# Power_And_Driver.net
KiCad netlist of a schematic drawn in Altium Designer
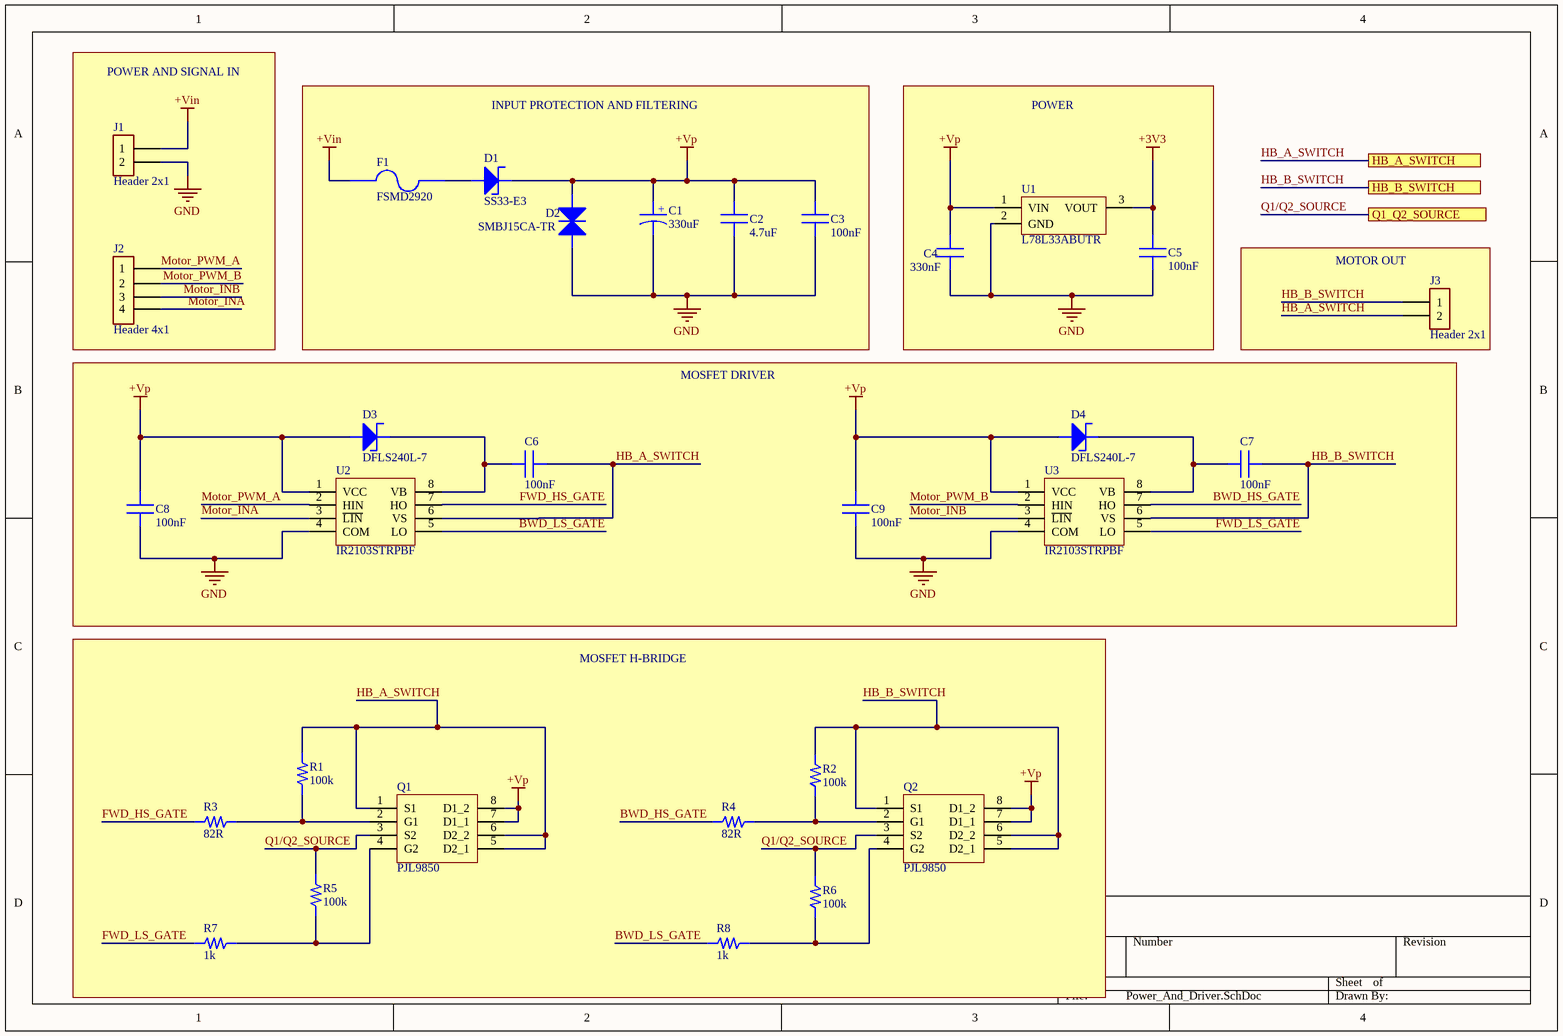
[diagram p0: Power_And_Driver.SchDoc]

(export (version "E")
  (design (tool "Eeschema 10.0.6"))
  (components
    (comp (ref "C1")
      (value "330uF")
      (footprint "CAP_EEEFK1V331P")
      (description "330 µF 35 V Aluminum Electrolytic Capacitors Radial, Can - SMD 2000 Hrs @ 105°C")
      (fields (field (name "TOLERANCE") "±20%") (field (name "MANUFACTURER") "Panasonic Industry"))
      (libsource (lib "Chicken_Coop_Door_Main_Board_V3") (part "CAP Electrolytic EEE-FK1V331P"))
    )
    (comp (ref "C2")
      (value "4.7uF")
      (footprint "CAPC2012X145N 0805")
      (description "MLCC (2012) 0805 4.7uF 16VDC ±10% X7R AUTOMOTIVE")
      (fields (field (name "TOLERANCE") "±10 %") (field (name "MANUFACTURER") "SAMSUNG"))
      (libsource (lib "Chicken_Coop_Door_Main_Board_V3") (part "CAP 0805 4.7uF CL21B475KOQVPNE"))
    )
    (comp (ref "C3")
      (value "100nF")
      (footprint "CAPC2012X145N 0805")
      (description "MLCC 0805 100nF 50VDC ±10% X7R")
      (fields (field (name "TOLERANCE") "±5 %") (field (name "MANUFACTURER") "YAGEO"))
      (libsource (lib "Chicken_Coop_Door_Main_Board_V3") (part "CAP 0805 100nF CC0805JRX7R9BB104"))
    )
    (comp (ref "C4")
      (value "330nF")
      (footprint "CAPC2012X145N 0805")
      (description "MLCC (2012) 0805 330nF 50VDC ±10% X7R")
      (fields (field (name "TOLERANCE") "±10 %") (field (name "MANUFACTURER") "SAMSUNG"))
      (libsource (lib "Chicken_Coop_Door_Main_Board_V3") (part "CAP 0805 330nF CL21B334KBFNNNE"))
    )
    (comp (ref "C5")
      (value "100nF")
      (footprint "CAPC2012X145N 0805")
      (description "MLCC 0805 100nF 50VDC ±10% X7R")
      (fields (field (name "TOLERANCE") "±5 %") (field (name "MANUFACTURER") "YAGEO"))
      (libsource (lib "Chicken_Coop_Door_Main_Board_V3") (part "CAP 0805 100nF CC0805JRX7R9BB104"))
    )
    (comp (ref "C6")
      (value "100nF")
      (footprint "CAPC2012X145N 0805")
      (description "MLCC 0805 100nF 50VDC ±10% X7R")
      (fields (field (name "TOLERANCE") "±5 %") (field (name "MANUFACTURER") "YAGEO"))
      (libsource (lib "Chicken_Coop_Door_Main_Board_V3") (part "CAP 0805 100nF CC0805JRX7R9BB104"))
    )
    (comp (ref "C7")
      (value "100nF")
      (footprint "CAPC2012X145N 0805")
      (description "MLCC 0805 100nF 50VDC ±10% X7R")
      (fields (field (name "TOLERANCE") "±5 %") (field (name "MANUFACTURER") "YAGEO"))
      (libsource (lib "Chicken_Coop_Door_Main_Board_V3") (part "CAP 0805 100nF CC0805JRX7R9BB104"))
    )
    (comp (ref "C8")
      (value "100nF")
      (footprint "CAPC2012X145N 0805")
      (description "MLCC 0805 100nF 50VDC ±10% X7R")
      (fields (field (name "TOLERANCE") "±5 %") (field (name "MANUFACTURER") "YAGEO"))
      (libsource (lib "Chicken_Coop_Door_Main_Board_V3") (part "CAP 0805 100nF CC0805JRX7R9BB104"))
    )
    (comp (ref "C9")
      (value "100nF")
      (footprint "CAPC2012X145N 0805")
      (description "MLCC 0805 100nF 50VDC ±10% X7R")
      (fields (field (name "TOLERANCE") "±5 %") (field (name "MANUFACTURER") "YAGEO"))
      (libsource (lib "Chicken_Coop_Door_Main_Board_V3") (part "CAP 0805 100nF CC0805JRX7R9BB104"))
    )
    (comp (ref "D1")
      (value "SS33-E3")
      (footprint "SS33-E3/57T Schottky Diode")
      (description "DIODE SCHOTTKY 30V 3A DO214AB")
      (fields (field (name "MANUFACTURER") "Vishay General Semiconductor - Diodes Division"))
      (libsource (lib "Chicken_Coop_Door_Main_Board_V3") (part "DIODE SCHOTTKY SS33-E3/57T"))
    )
    (comp (ref "D2")
      (value "SMBJ15CA-TR")
      (footprint "TVS DIODE SMBJ15CA-TR")
      (description "24.4V Clamp 25.1A Ipp Tvs Diode Surface Mount SMB")
      (fields (field (name "MANUFACTURER") "STMicroelectronics"))
      (libsource (lib "Chicken_Coop_Door_Main_Board_V3") (part "TVS DIODE SMBJ15CA-TR"))
    )
    (comp (ref "D3")
      (value "DFLS240L-7")
      (footprint "DIODE DFLS240L-7  POWERDI 123")
      (description "DIODE SCHOTTK 40V 2A POWERDI 123")
      (fields (field (name "MANUFACTURER") "Diodes Incorporated"))
      (libsource (lib "Chicken_Coop_Door_Main_Board_V3") (part "DIODE SCHOTTKY DFLS240L-7"))
    )
    (comp (ref "D4")
      (value "DFLS240L-7")
      (footprint "DIODE DFLS240L-7  POWERDI 123")
      (description "DIODE SCHOTTK 40V 2A POWERDI 123")
      (fields (field (name "MANUFACTURER") "Diodes Incorporated"))
      (libsource (lib "Chicken_Coop_Door_Main_Board_V3") (part "DIODE SCHOTTKY DFLS240L-7"))
    )
    (comp (ref "F1")
      (value "FSMD2920")
      (footprint "FUSE FSMD200-24-2920-R")
      (description "PTC Resettable Fuse 24V 2 A Ih Surface Mount 2920 (7351 Metric), Concave")
      (fields (field (name "MANUFACTURER") "RFE/Fuzetec"))
      (libsource (lib "Chicken_Coop_Door_Main_Board_V3") (part "FUSE FSMD200-24-2920-R"))
    )
    (comp (ref "J1")
      (value "Header 2x1")
      (footprint "2x1 Terminal Block")
      (description "TERM.BLK.5.00MM 2P PCB TYPE GREEN")
      (fields (field (name "MANUFACTURER") "DEGSON") (field (name "VOLTAGE") "300V"))
      (libsource (lib "Chicken_Coop_Door_Main_Board_V3") (part "Terminal Block 2x1"))
    )
    (comp (ref "J2")
      (value "Header 4x1")
      (footprint "JST_B4B-PH-K-S 1x4 Header")
      (description "CON.T.B.2MM 4P 180C MALE WHITE CONNFLY")
      (fields (field (name "MANUFACTURER") "CONNFLY"))
      (libsource (lib "Chicken_Coop_Door_Main_Board_V3") (part "Header 4x1 DS1066-4MVW6X"))
    )
    (comp (ref "J3")
      (value "Header 2x1")
      (footprint "2x1 Terminal Block")
      (description "TERM.BLK.5.00MM 2P PCB TYPE GREEN")
      (fields (field (name "MANUFACTURER") "DEGSON") (field (name "VOLTAGE") "300V"))
      (libsource (lib "") (part "Terminal Block 2x1_1"))
    )
    (comp (ref "Q1")
      (value "PJL9850")
      (footprint "PJL850 N-CH MOSFET")
      (description "Low Voltage MOSFET (20-40V,Rds(on)<1) - PJL9850 , N/N Channel, Dual, 5.4A, 40V, SOP-8")
      (fields (field (name "MANUFACTURER") "PANJIT"))
      (libsource (lib "Chicken_Coop_Door_Main_Board_V3") (part "PJL9850 N-Ch MOSFET"))
    )
    (comp (ref "Q2")
      (value "PJL9850")
      (footprint "PJL850 N-CH MOSFET")
      (description "Low Voltage MOSFET (20-40V,Rds(on)<1) - PJL9850 , N/N Channel, Dual, 5.4A, 40V, SOP-8")
      (fields (field (name "MANUFACTURER") "PANJIT"))
      (libsource (lib "Chicken_Coop_Door_Main_Board_V3") (part "PJL9850 N-Ch MOSFET"))
    )
    (comp (ref "R1")
      (value "100k")
      (footprint "RES 0603 ROYALOHM")
      (description "RES.(1608) 0603 100K Ohms 1% 1/10W-S 100PPM")
      (fields (field (name "TOLERANCE") "±5 %") (field (name "MANUFACTURER") "ROYALOHM"))
      (libsource (lib "Chicken_Coop_Door_Main_Board_V3") (part "RES 0603 100k 0603SAF1003T5E"))
    )
    (comp (ref "R2")
      (value "100k")
      (footprint "RES 0603 ROYALOHM")
      (description "RES.(1608) 0603 100K Ohms 1% 1/10W-S 100PPM")
      (fields (field (name "TOLERANCE") "±5 %") (field (name "MANUFACTURER") "ROYALOHM"))
      (libsource (lib "Chicken_Coop_Door_Main_Board_V3") (part "RES 0603 100k 0603SAF1003T5E"))
    )
    (comp (ref "R3")
      (value "82R")
      (footprint "RES 0805 YAGEO C2012X60N")
      (description "RES.(2012) 0805 82 Ohms 5% 1/8W-S 200PPM")
      (fields (field (name "POWER") "1/8W") (field (name "TOLERANCE") "±1 %"))
      (libsource (lib "Chicken_Coop_Door_Main_Board_V3") (part "RES 0805 82 Ohms 0805S8J0820T5E"))
    )
    (comp (ref "R4")
      (value "82R")
      (footprint "RES 0805 YAGEO C2012X60N")
      (description "RES.(2012) 0805 82 Ohms 5% 1/8W-S 200PPM")
      (fields (field (name "POWER") "1/8W") (field (name "TOLERANCE") "±1 %"))
      (libsource (lib "Chicken_Coop_Door_Main_Board_V3") (part "RES 0805 82 Ohms 0805S8J0820T5E"))
    )
    (comp (ref "R5")
      (value "100k")
      (footprint "RES 0603 ROYALOHM")
      (description "RES.(1608) 0603 100K Ohms 1% 1/10W-S 100PPM")
      (fields (field (name "TOLERANCE") "±5 %") (field (name "MANUFACTURER") "ROYALOHM"))
      (libsource (lib "Chicken_Coop_Door_Main_Board_V3") (part "RES 0603 100k 0603SAF1003T5E"))
    )
    (comp (ref "R6")
      (value "100k")
      (footprint "RES 0603 ROYALOHM")
      (description "RES.(1608) 0603 100K Ohms 1% 1/10W-S 100PPM")
      (fields (field (name "TOLERANCE") "±5 %") (field (name "MANUFACTURER") "ROYALOHM"))
      (libsource (lib "Chicken_Coop_Door_Main_Board_V3") (part "RES 0603 100k 0603SAF1003T5E"))
    )
    (comp (ref "R7")
      (value "1k")
      (footprint "RES 0805 YAGEO C2012X60N")
      (description "RES.(2012) 0805 1K Ohms 1% 1/8W-S 100PPM")
      (fields (field (name "POWER") "1/8W") (field (name "TOLERANCE") "±1 %"))
      (libsource (lib "Chicken_Coop_Door_Main_Board_V3") (part "RES 0805 1k Ohms 0805S8F1001TDE"))
    )
    (comp (ref "R8")
      (value "1k")
      (footprint "RES 0805 YAGEO C2012X60N")
      (description "RES.(2012) 0805 1K Ohms 1% 1/8W-S 100PPM")
      (fields (field (name "POWER") "1/8W") (field (name "TOLERANCE") "±1 %"))
      (libsource (lib "Chicken_Coop_Door_Main_Board_V3") (part "RES 0805 1k Ohms 0805S8F1001TDE"))
    )
    (comp (ref "U1")
      (value "L78L33ABUTR")
      (footprint "LDO L78L33ABUTR SOT89")
      (description "Linear Voltage Regulator IC Positive Fixed 1 Output 100mA SOT-89-3")
      (fields (field (name "MANUFACTURER") "STMicroelectronics"))
      (libsource (lib "Chicken_Coop_Door_Main_Board_V3") (part "LDO L78L33ABUTR"))
    )
    (comp (ref "U2")
      (value "IR2103STRPBF")
      (footprint "IR2103STRPBF Half Bridge Mosfet Driver")
      (description "Half-Bridge Gate Driver IC Inverting, Non-Inverting 8-SOIC")
      (fields (field (name "MANUFACTURER") "Infineon Technologies"))
      (libsource (lib "Chicken_Coop_Door_Main_Board_V3") (part "IR2103STRPBF Half Bridge MOSFET Driver"))
    )
    (comp (ref "U3")
      (value "IR2103STRPBF")
      (footprint "IR2103STRPBF Half Bridge Mosfet Driver")
      (description "Half-Bridge Gate Driver IC Inverting, Non-Inverting 8-SOIC")
      (fields (field (name "MANUFACTURER") "Infineon Technologies"))
      (libsource (lib "Chicken_Coop_Door_Main_Board_V3") (part "IR2103STRPBF Half Bridge MOSFET Driver"))
    )
  )
  (nets
    (net (code "1") (name "+3V3") (class "Default")
      (node (ref "C5") (pin "2") (pinfunction "2_2") (pintype "passive"))
      (node (ref "U1") (pin "3") (pinfunction "VOUT_3") (pintype "passive"))
    )
    (net (code "2") (name "+Vin") (class "Default")
      (node (ref "F1") (pin "1") (pinfunction "1_1") (pintype "passive"))
      (node (ref "J1") (pin "1") (pinfunction "1_1") (pintype "passive"))
    )
    (net (code "3") (name "+Vp") (class "Default")
      (node (ref "C1") (pin "1") (pinfunction "1_1") (pintype "passive"))
      (node (ref "C2") (pin "2") (pinfunction "2_2") (pintype "passive"))
      (node (ref "C3") (pin "2") (pinfunction "2_2") (pintype "passive"))
      (node (ref "C4") (pin "2") (pinfunction "2_2") (pintype "passive"))
      (node (ref "C8") (pin "2") (pinfunction "2_2") (pintype "passive"))
      (node (ref "C9") (pin "2") (pinfunction "2_2") (pintype "passive"))
      (node (ref "D1") (pin "K") (pinfunction "Cathode_K") (pintype "passive"))
      (node (ref "D2") (pin "2") (pinfunction "C_2") (pintype "passive"))
      (node (ref "D3") (pin "1") (pinfunction "Anode_1") (pintype "passive"))
      (node (ref "D4") (pin "1") (pinfunction "Anode_1") (pintype "passive"))
      (node (ref "Q1") (pin "7") (pinfunction "D1_1_7") (pintype "passive"))
      (node (ref "Q1") (pin "8") (pinfunction "D1_2_8") (pintype "passive"))
      (node (ref "Q2") (pin "7") (pinfunction "D1_1_7") (pintype "passive"))
      (node (ref "Q2") (pin "8") (pinfunction "D1_2_8") (pintype "passive"))
      (node (ref "U1") (pin "1") (pinfunction "VIN_1") (pintype "passive"))
      (node (ref "U2") (pin "1") (pinfunction "VCC_1") (pintype "passive"))
      (node (ref "U3") (pin "1") (pinfunction "VCC_1") (pintype "passive"))
    )
    (net (code "4") (name "/BWD_HS_GATE") (class "Default")
      (node (ref "R4") (pin "1") (pinfunction "1_1") (pintype "passive"))
      (node (ref "U3") (pin "7") (pinfunction "HO_7") (pintype "passive"))
    )
    (net (code "5") (name "/BWD_LS_GATE") (class "Default")
      (node (ref "R8") (pin "1") (pinfunction "1_1") (pintype "passive"))
      (node (ref "U2") (pin "5") (pinfunction "LO_5") (pintype "passive"))
    )
    (net (code "6") (name "/FWD_HS_GATE") (class "Default")
      (node (ref "R3") (pin "1") (pinfunction "1_1") (pintype "passive"))
      (node (ref "U2") (pin "7") (pinfunction "HO_7") (pintype "passive"))
    )
    (net (code "7") (name "/FWD_LS_GATE") (class "Default")
      (node (ref "R7") (pin "1") (pinfunction "1_1") (pintype "passive"))
      (node (ref "U3") (pin "5") (pinfunction "LO_5") (pintype "passive"))
    )
    (net (code "8") (name "/HB_A_SWITCH") (class "Default")
      (node (ref "C6") (pin "1") (pinfunction "1_1") (pintype "passive"))
      (node (ref "J3") (pin "2") (pinfunction "2_2") (pintype "passive"))
      (node (ref "Q1") (pin "1") (pinfunction "S1_1") (pintype "passive"))
      (node (ref "Q1") (pin "5") (pinfunction "D2_1_5") (pintype "passive"))
      (node (ref "Q1") (pin "6") (pinfunction "D2_2_6") (pintype "passive"))
      (node (ref "R1") (pin "2") (pinfunction "2_2") (pintype "passive"))
      (node (ref "U2") (pin "6") (pinfunction "VS_6") (pintype "passive"))
    )
    (net (code "9") (name "/HB_B_SWITCH") (class "Default")
      (node (ref "C7") (pin "1") (pinfunction "1_1") (pintype "passive"))
      (node (ref "J3") (pin "1") (pinfunction "1_1") (pintype "passive"))
      (node (ref "Q2") (pin "1") (pinfunction "S1_1") (pintype "passive"))
      (node (ref "Q2") (pin "5") (pinfunction "D2_1_5") (pintype "passive"))
      (node (ref "Q2") (pin "6") (pinfunction "D2_2_6") (pintype "passive"))
      (node (ref "R2") (pin "2") (pinfunction "2_2") (pintype "passive"))
      (node (ref "U3") (pin "6") (pinfunction "VS_6") (pintype "passive"))
    )
    (net (code "10") (name "/Motor_INA") (class "Default")
      (node (ref "J2") (pin "4") (pinfunction "4_4") (pintype "passive"))
      (node (ref "U2") (pin "3") (pinfunction "~{LIN}_3") (pintype "passive"))
    )
    (net (code "11") (name "/Motor_INB") (class "Default")
      (node (ref "J2") (pin "3") (pinfunction "3_3") (pintype "passive"))
      (node (ref "U3") (pin "3") (pinfunction "~{LIN}_3") (pintype "passive"))
    )
    (net (code "12") (name "/Motor_PWM_A") (class "Default")
      (node (ref "J2") (pin "1") (pinfunction "1_1") (pintype "passive"))
      (node (ref "U2") (pin "2") (pinfunction "HIN_2") (pintype "passive"))
    )
    (net (code "13") (name "/Motor_PWM_B") (class "Default")
      (node (ref "J2") (pin "2") (pinfunction "2_2") (pintype "passive"))
      (node (ref "U3") (pin "2") (pinfunction "HIN_2") (pintype "passive"))
    )
    (net (code "14") (name "/Q1{slash}Q2_SOURCE") (class "Default")
      (node (ref "Q1") (pin "3") (pinfunction "S2_3") (pintype "passive"))
      (node (ref "Q2") (pin "3") (pinfunction "S2_3") (pintype "passive"))
      (node (ref "R5") (pin "2") (pinfunction "2_2") (pintype "passive"))
      (node (ref "R6") (pin "2") (pinfunction "2_2") (pintype "passive"))
    )
    (net (code "15") (name "GND") (class "Default")
      (node (ref "C1") (pin "2") (pinfunction "2_2") (pintype "passive"))
      (node (ref "C2") (pin "1") (pinfunction "1_1") (pintype "passive"))
      (node (ref "C3") (pin "1") (pinfunction "1_1") (pintype "passive"))
      (node (ref "C4") (pin "1") (pinfunction "1_1") (pintype "passive"))
      (node (ref "C5") (pin "1") (pinfunction "1_1") (pintype "passive"))
      (node (ref "C8") (pin "1") (pinfunction "1_1") (pintype "passive"))
      (node (ref "C9") (pin "1") (pinfunction "1_1") (pintype "passive"))
      (node (ref "D2") (pin "1") (pinfunction "A_1") (pintype "passive"))
      (node (ref "J1") (pin "2") (pinfunction "2_2") (pintype "passive"))
      (node (ref "U1") (pin "2") (pinfunction "GND_2") (pintype "passive"))
      (node (ref "U2") (pin "4") (pinfunction "COM_4") (pintype "passive"))
      (node (ref "U3") (pin "4") (pinfunction "COM_4") (pintype "passive"))
    )
    (net (code "16") (name "Net-(D1-Anode)") (class "Default")
      (node (ref "D1") (pin "A") (pinfunction "Anode_A") (pintype "passive"))
      (node (ref "F1") (pin "2") (pinfunction "2_2") (pintype "passive"))
    )
    (net (code "17") (name "Net-(D3-Cathode)") (class "Default")
      (node (ref "C6") (pin "2") (pinfunction "2_2") (pintype "passive"))
      (node (ref "D3") (pin "2") (pinfunction "Cathode_2") (pintype "passive"))
      (node (ref "U2") (pin "8") (pinfunction "VB_8") (pintype "passive"))
    )
    (net (code "18") (name "Net-(D4-Cathode)") (class "Default")
      (node (ref "C7") (pin "2") (pinfunction "2_2") (pintype "passive"))
      (node (ref "D4") (pin "2") (pinfunction "Cathode_2") (pintype "passive"))
      (node (ref "U3") (pin "8") (pinfunction "VB_8") (pintype "passive"))
    )
    (net (code "19") (name "Net-(Q1-G1)") (class "Default")
      (node (ref "Q1") (pin "2") (pinfunction "G1_2") (pintype "passive"))
      (node (ref "R1") (pin "1") (pinfunction "1_1") (pintype "passive"))
      (node (ref "R3") (pin "2") (pinfunction "2_2") (pintype "passive"))
    )
    (net (code "20") (name "Net-(Q1-G2)") (class "Default")
      (node (ref "Q1") (pin "4") (pinfunction "G2_4") (pintype "passive"))
      (node (ref "R5") (pin "1") (pinfunction "1_1") (pintype "passive"))
      (node (ref "R7") (pin "2") (pinfunction "2_2") (pintype "passive"))
    )
    (net (code "21") (name "Net-(Q2-G1)") (class "Default")
      (node (ref "Q2") (pin "2") (pinfunction "G1_2") (pintype "passive"))
      (node (ref "R2") (pin "1") (pinfunction "1_1") (pintype "passive"))
      (node (ref "R4") (pin "2") (pinfunction "2_2") (pintype "passive"))
    )
    (net (code "22") (name "Net-(Q2-G2)") (class "Default")
      (node (ref "Q2") (pin "4") (pinfunction "G2_4") (pintype "passive"))
      (node (ref "R6") (pin "1") (pinfunction "1_1") (pintype "passive"))
      (node (ref "R8") (pin "2") (pinfunction "2_2") (pintype "passive"))
    )
  )
)
